# 4_-_IO_Socket_2.net
KiCad netlist of a schematic drawn in Altium Designer
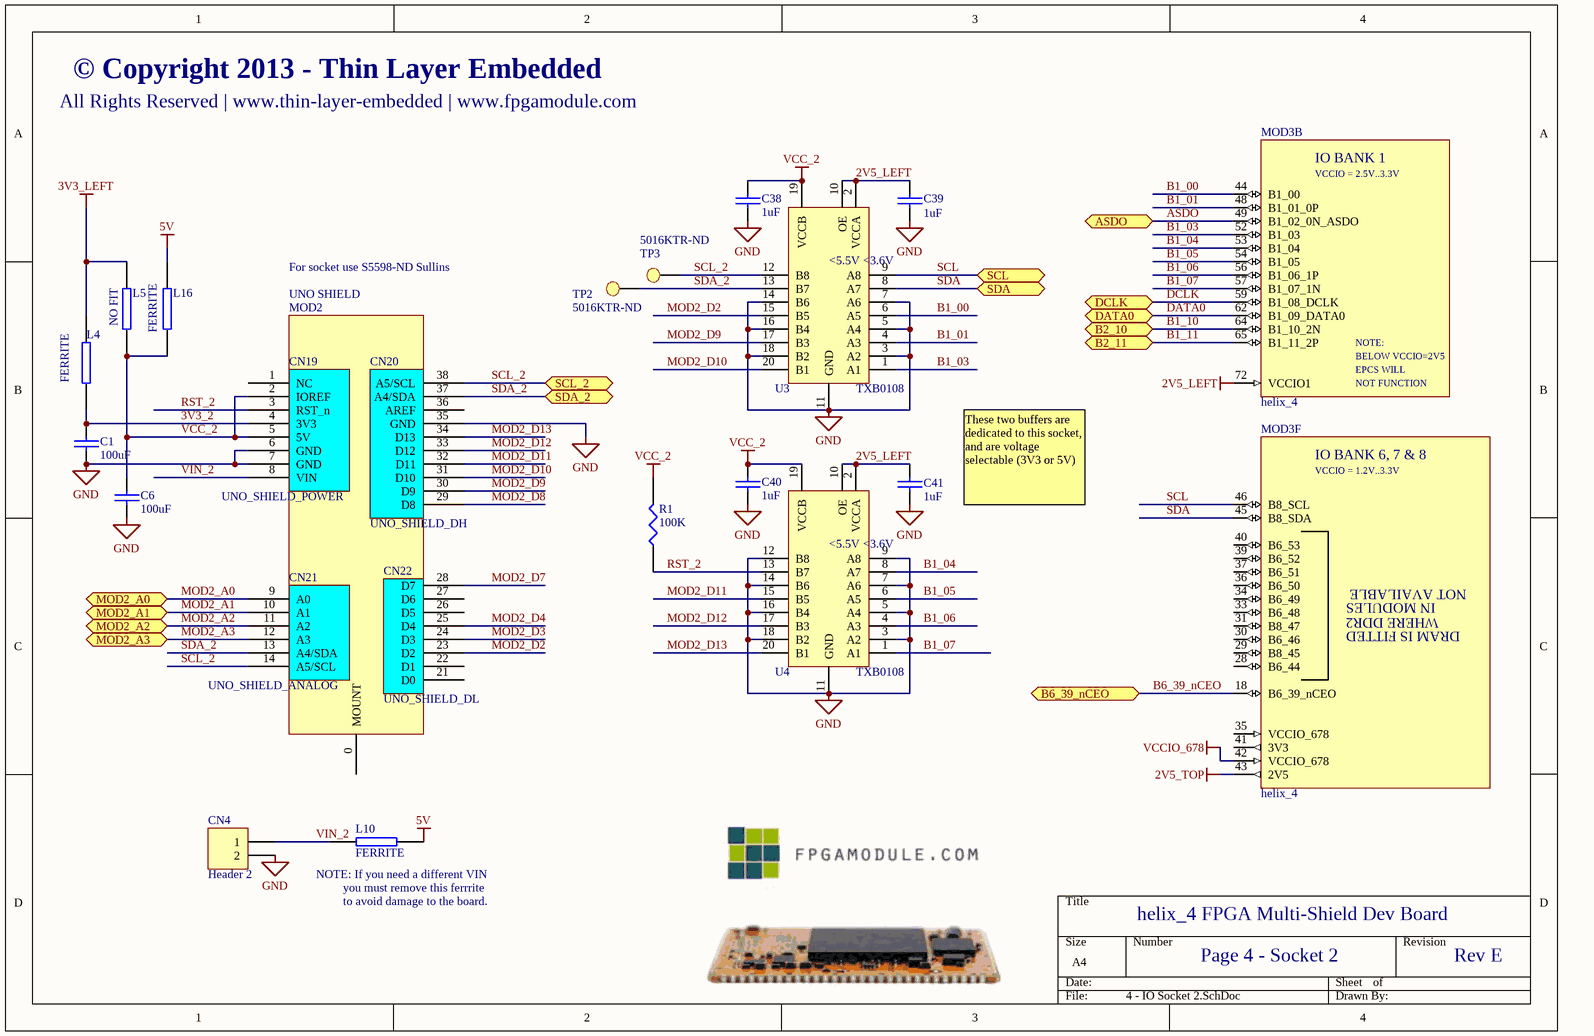
[diagram p0: 4 - IO Socket 2.SchDoc]

(export (version "E")
  (design (tool "Eeschema 10.0.6"))
  (components
    (comp (ref "C1")
      (value "100uF")
      (footprint "1210")
      (description "Capacitor")
      (libsource (lib "*") (part "CAP"))
    )
    (comp (ref "C6")
      (value "100uF")
      (footprint "1210")
      (description "Capacitor")
      (libsource (lib "*") (part "CAP"))
    )
    (comp (ref "C38")
      (value "1uF")
      (footprint "0805")
      (description "Capacitor")
      (libsource (lib "*") (part "CAP"))
    )
    (comp (ref "C39")
      (value "1uF")
      (footprint "0805")
      (description "Capacitor")
      (libsource (lib "*") (part "CAP"))
    )
    (comp (ref "C40")
      (value "1uF")
      (footprint "0805")
      (description "Capacitor")
      (libsource (lib "*") (part "CAP"))
    )
    (comp (ref "C41")
      (value "1uF")
      (footprint "0805")
      (description "Capacitor")
      (libsource (lib "*") (part "CAP"))
    )
    (comp (ref "CN4")
      (value "Header 2")
      (footprint "HDR1X2")
      (description "Header, 2-Pin")
      (fields (field (name "PUBLISHER") "Altium Limited"))
      (libsource (lib "Miscellaneous Connectors") (part "Header 2"))
    )
    (comp (ref "CN19")
      (value "UNO_SHIELD_POWER")
      (footprint "UNO_SHIELD_POWER")
      (libsource (lib "master_library") (part "UNO_SHIELD_POWER"))
    )
    (comp (ref "CN20")
      (value "UNO_SHIELD_DH")
      (footprint "UNO_SHIELD_DH")
      (libsource (lib "master_library") (part "UNO_SHIELD_DH"))
    )
    (comp (ref "CN21")
      (value "UNO_SHIELD_ANALOG")
      (footprint "UNO_SHIELD_ANALOG")
      (libsource (lib "master_library") (part "UNO_SHIELD_ANALOG"))
    )
    (comp (ref "CN22")
      (value "UNO_SHIELD_DL")
      (footprint "UNO_SHIELD_DL")
      (libsource (lib "master_library") (part "UNO_SHIELD_DL"))
    )
    (comp (ref "L4") (value "FERRITE") (footprint "0805") (libsource (lib "*") (part "FERRITE")))
    (comp (ref "L5")
      (value "NO FIT")
      (footprint "0805")
      (description "FERRITE")
      (libsource (lib "*") (part "FERRITE"))
    )
    (comp (ref "L10") (value "FERRITE") (footprint "0805") (libsource (lib "*") (part "FERRITE")))
    (comp (ref "L16") (value "FERRITE") (footprint "0805") (libsource (lib "*") (part "FERRITE")))
    (comp (ref "MOD2")
      (value "UNO SHIELD")
      (footprint "UNO_SHIELD_MECH")
      (libsource (lib "master_library") (part "UNO_SHIELD_MECH"))
    )
    (comp (ref "MOD3")
      (value "helix_4")
      (footprint "HELIX_4_LCC104_HOST")
      (libsource (lib "master_library") (part "helix_4 Rev C Module"))
    )
    (comp (ref "R1") (value "100K") (footprint "0805") (libsource (lib "*") (part "RES1")))
    (comp (ref "TP2")
      (value "Test Point")
      (footprint "TEST_POINT")
      (fields (field (name "SUPPLIER PART NUMBER 2") "5016KTR-ND"))
      (libsource (lib "motion tracker r2") (part "Test Point"))
    )
    (comp (ref "TP3")
      (value "Test Point")
      (footprint "TEST_POINT")
      (fields (field (name "SUPPLIER PART NUMBER 2") "5016KTR-ND"))
      (libsource (lib "motion tracker r2") (part "Test Point"))
    )
    (comp (ref "U3")
      (value "TXB0108")
      (footprint "TSSOP20")
      (description "TI Bir-dir buffer")
      (libsource (lib "master_library") (part "TXB0108"))
    )
    (comp (ref "U4")
      (value "TXB0108")
      (footprint "TSSOP20")
      (description "TI Bir-dir buffer")
      (libsource (lib "master_library") (part "TXB0108"))
    )
  )
  (nets
    (net (code "1") (name "/3V3_2") (class "Default")
      (node (ref "C1") (pin "1") (pinfunction "1_1") (pintype "passive"))
      (node (ref "CN19") (pin "4") (pinfunction "3V3_4") (pintype "passive"))
      (node (ref "L4") (pin "2") (pinfunction "2_2") (pintype "passive"))
    )
    (net (code "2") (name "/ASDO") (class "Default")
      (node (ref "MOD3") (pin "49") (pinfunction "B1_02_0N_ASDO_49") (pintype "bidirectional"))
    )
    (net (code "3") (name "/B1_00") (class "Default")
      (node (ref "MOD3") (pin "44") (pinfunction "B1_00_44") (pintype "bidirectional"))
      (node (ref "U3") (pin "6") (pinfunction "A5_6") (pintype "passive"))
    )
    (net (code "4") (name "/B1_01") (class "Default")
      (node (ref "MOD3") (pin "48") (pinfunction "B1_01_0P_48") (pintype "bidirectional"))
      (node (ref "U3") (pin "4") (pinfunction "A3_4") (pintype "passive"))
    )
    (net (code "5") (name "/B1_03") (class "Default")
      (node (ref "MOD3") (pin "52") (pinfunction "B1_03_52") (pintype "bidirectional"))
      (node (ref "U3") (pin "1") (pinfunction "A1_1") (pintype "passive"))
    )
    (net (code "6") (name "/B1_04") (class "Default")
      (node (ref "MOD3") (pin "53") (pinfunction "B1_04_53") (pintype "bidirectional"))
      (node (ref "U4") (pin "8") (pinfunction "A7_8") (pintype "passive"))
    )
    (net (code "7") (name "/B1_05") (class "Default")
      (node (ref "MOD3") (pin "54") (pinfunction "B1_05_54") (pintype "bidirectional"))
      (node (ref "U4") (pin "6") (pinfunction "A5_6") (pintype "passive"))
    )
    (net (code "8") (name "/B1_06") (class "Default")
      (node (ref "MOD3") (pin "56") (pinfunction "B1_06_1P_56") (pintype "bidirectional"))
      (node (ref "U4") (pin "4") (pinfunction "A3_4") (pintype "passive"))
    )
    (net (code "9") (name "/B1_07") (class "Default")
      (node (ref "MOD3") (pin "57") (pinfunction "B1_07_1N_57") (pintype "bidirectional"))
      (node (ref "U4") (pin "1") (pinfunction "A1_1") (pintype "passive"))
    )
    (net (code "10") (name "/B1_10") (class "Default")
      (node (ref "MOD3") (pin "64") (pinfunction "B1_10_2N_64") (pintype "bidirectional"))
    )
    (net (code "11") (name "/B1_11") (class "Default")
      (node (ref "MOD3") (pin "65") (pinfunction "B1_11_2P_65") (pintype "bidirectional"))
    )
    (net (code "12") (name "/B6_39_nCEO") (class "Default")
      (node (ref "MOD3") (pin "18") (pinfunction "B6_39_nCEO_18") (pintype "bidirectional"))
    )
    (net (code "13") (name "/DATA0") (class "Default")
      (node (ref "MOD3") (pin "62") (pinfunction "B1_09_DATA0_62") (pintype "bidirectional"))
    )
    (net (code "14") (name "/DCLK") (class "Default")
      (node (ref "MOD3") (pin "59") (pinfunction "B1_08_DCLK_59") (pintype "bidirectional"))
    )
    (net (code "15") (name "/MOD2_A0") (class "Default")
      (node (ref "CN21") (pin "9") (pinfunction "A0_9") (pintype "passive"))
    )
    (net (code "16") (name "/MOD2_A1") (class "Default")
      (node (ref "CN21") (pin "10") (pinfunction "A1_10") (pintype "passive"))
    )
    (net (code "17") (name "/MOD2_A2") (class "Default")
      (node (ref "CN21") (pin "11") (pinfunction "A2_11") (pintype "passive"))
    )
    (net (code "18") (name "/MOD2_A3") (class "Default")
      (node (ref "CN21") (pin "12") (pinfunction "A3_12") (pintype "passive"))
    )
    (net (code "19") (name "/MOD2_D2") (class "Default")
      (node (ref "CN22") (pin "23") (pinfunction "D2_23") (pintype "passive"))
      (node (ref "U3") (pin "15") (pinfunction "B5_15") (pintype "passive"))
    )
    (net (code "20") (name "/MOD2_D3") (class "Default")
      (node (ref "CN22") (pin "24") (pinfunction "D3_24") (pintype "passive"))
    )
    (net (code "21") (name "/MOD2_D4") (class "Default")
      (node (ref "CN22") (pin "25") (pinfunction "D4_25") (pintype "passive"))
    )
    (net (code "22") (name "/MOD2_D7") (class "Default")
      (node (ref "CN22") (pin "28") (pinfunction "D7_28") (pintype "passive"))
    )
    (net (code "23") (name "/MOD2_D8") (class "Default")
      (node (ref "CN20") (pin "29") (pinfunction "D8_29") (pintype "passive"))
    )
    (net (code "24") (name "/MOD2_D9") (class "Default")
      (node (ref "CN20") (pin "30") (pinfunction "D9_30") (pintype "passive"))
      (node (ref "U3") (pin "17") (pinfunction "B3_17") (pintype "passive"))
    )
    (net (code "25") (name "/MOD2_D10") (class "Default")
      (node (ref "CN20") (pin "31") (pinfunction "D10_31") (pintype "passive"))
      (node (ref "U3") (pin "20") (pinfunction "B1_20") (pintype "passive"))
    )
    (net (code "26") (name "/MOD2_D11") (class "Default")
      (node (ref "CN20") (pin "32") (pinfunction "D11_32") (pintype "passive"))
      (node (ref "U4") (pin "15") (pinfunction "B5_15") (pintype "passive"))
    )
    (net (code "27") (name "/MOD2_D12") (class "Default")
      (node (ref "CN20") (pin "33") (pinfunction "D12_33") (pintype "passive"))
      (node (ref "U4") (pin "17") (pinfunction "B3_17") (pintype "passive"))
    )
    (net (code "28") (name "/MOD2_D13") (class "Default")
      (node (ref "CN20") (pin "34") (pinfunction "D13_34") (pintype "passive"))
      (node (ref "U4") (pin "20") (pinfunction "B1_20") (pintype "passive"))
    )
    (net (code "29") (name "/RST_2") (class "Default")
      (node (ref "CN19") (pin "3") (pinfunction "RST_n_3") (pintype "passive"))
      (node (ref "R1") (pin "1") (pinfunction "1_1") (pintype "passive"))
      (node (ref "U4") (pin "13") (pinfunction "B7_13") (pintype "passive"))
    )
    (net (code "30") (name "/SCL") (class "Default")
      (node (ref "MOD3") (pin "46") (pinfunction "B8_SCL_46") (pintype "bidirectional"))
      (node (ref "U3") (pin "9") (pinfunction "A8_9") (pintype "passive"))
    )
    (net (code "31") (name "/SCL_2") (class "Default")
      (node (ref "CN20") (pin "38") (pinfunction "A5/SCL_38") (pintype "passive"))
      (node (ref "CN21") (pin "14") (pinfunction "A5/SCL_14") (pintype "passive"))
      (node (ref "TP3") (pin "1") (pinfunction "1_1") (pintype "passive"))
      (node (ref "U3") (pin "12") (pinfunction "B8_12") (pintype "passive"))
    )
    (net (code "32") (name "/SDA") (class "Default")
      (node (ref "MOD3") (pin "45") (pinfunction "B8_SDA_45") (pintype "bidirectional"))
      (node (ref "U3") (pin "8") (pinfunction "A7_8") (pintype "passive"))
    )
    (net (code "33") (name "/SDA_2") (class "Default")
      (node (ref "CN20") (pin "37") (pinfunction "A4/SDA_37") (pintype "passive"))
      (node (ref "CN21") (pin "13") (pinfunction "A4/SDA_13") (pintype "passive"))
      (node (ref "TP2") (pin "1") (pinfunction "1_1") (pintype "passive"))
      (node (ref "U3") (pin "13") (pinfunction "B7_13") (pintype "passive"))
    )
    (net (code "34") (name "/VIN_2") (class "Default")
      (node (ref "CN19") (pin "8") (pinfunction "VIN_8") (pintype "passive"))
      (node (ref "CN4") (pin "1") (pinfunction "1_1") (pintype "passive"))
      (node (ref "L10") (pin "2") (pinfunction "2_2") (pintype "passive"))
    )
    (net (code "35") (name "2V5_LEFT") (class "Default")
      (node (ref "C39") (pin "2") (pinfunction "2_2") (pintype "passive"))
      (node (ref "C41") (pin "2") (pinfunction "2_2") (pintype "passive"))
      (node (ref "MOD3") (pin "72") (pinfunction "VCCIO1_72") (pintype "input"))
      (node (ref "U3") (pin "10") (pinfunction "OE_10") (pintype "passive"))
      (node (ref "U3") (pin "2") (pinfunction "VCCA_2") (pintype "passive"))
      (node (ref "U4") (pin "10") (pinfunction "OE_10") (pintype "passive"))
      (node (ref "U4") (pin "2") (pinfunction "VCCA_2") (pintype "passive"))
    )
    (net (code "36") (name "2V5_TOP") (class "Default")
      (node (ref "MOD3") (pin "43") (pinfunction "2V5_43") (pintype "output"))
    )
    (net (code "37") (name "3V3_LEFT") (class "Default")
      (node (ref "L4") (pin "1") (pinfunction "1_1") (pintype "passive"))
      (node (ref "L5") (pin "1") (pinfunction "1_1") (pintype "passive"))
    )
    (net (code "38") (name "5V") (class "Default")
      (node (ref "L10") (pin "1") (pinfunction "1_1") (pintype "passive"))
      (node (ref "L16") (pin "1") (pinfunction "1_1") (pintype "passive"))
    )
    (net (code "39") (name "GND") (class "Default")
      (node (ref "C1") (pin "2") (pinfunction "2_2") (pintype "passive"))
      (node (ref "C38") (pin "1") (pinfunction "1_1") (pintype "passive"))
      (node (ref "C39") (pin "1") (pinfunction "1_1") (pintype "passive"))
      (node (ref "C40") (pin "1") (pinfunction "1_1") (pintype "passive"))
      (node (ref "C41") (pin "1") (pinfunction "1_1") (pintype "passive"))
      (node (ref "C6") (pin "2") (pinfunction "2_2") (pintype "passive"))
      (node (ref "CN19") (pin "6") (pinfunction "GND_6") (pintype "passive"))
      (node (ref "CN19") (pin "7") (pinfunction "GND_7") (pintype "passive"))
      (node (ref "CN20") (pin "35") (pinfunction "GND_35") (pintype "passive"))
      (node (ref "CN4") (pin "2") (pinfunction "2_2") (pintype "passive"))
      (node (ref "U3") (pin "11") (pinfunction "GND_11") (pintype "passive"))
      (node (ref "U3") (pin "14") (pinfunction "B6_14") (pintype "passive"))
      (node (ref "U3") (pin "16") (pinfunction "B4_16") (pintype "passive"))
      (node (ref "U3") (pin "18") (pinfunction "B2_18") (pintype "passive"))
      (node (ref "U3") (pin "3") (pinfunction "A2_3") (pintype "passive"))
      (node (ref "U3") (pin "5") (pinfunction "A4_5") (pintype "passive"))
      (node (ref "U3") (pin "7") (pinfunction "A6_7") (pintype "passive"))
      (node (ref "U4") (pin "11") (pinfunction "GND_11") (pintype "passive"))
      (node (ref "U4") (pin "12") (pinfunction "B8_12") (pintype "passive"))
      (node (ref "U4") (pin "14") (pinfunction "B6_14") (pintype "passive"))
      (node (ref "U4") (pin "16") (pinfunction "B4_16") (pintype "passive"))
      (node (ref "U4") (pin "18") (pinfunction "B2_18") (pintype "passive"))
      (node (ref "U4") (pin "3") (pinfunction "A2_3") (pintype "passive"))
      (node (ref "U4") (pin "5") (pinfunction "A4_5") (pintype "passive"))
      (node (ref "U4") (pin "7") (pinfunction "A6_7") (pintype "passive"))
      (node (ref "U4") (pin "9") (pinfunction "A8_9") (pintype "passive"))
    )
    (net (code "40") (name "VCCIO_678") (class "Default")
      (node (ref "MOD3") (pin "42") (pinfunction "VCCIO_678_42") (pintype "input"))
    )
    (net (code "41") (name "VCC_2") (class "Default")
      (node (ref "C38") (pin "2") (pinfunction "2_2") (pintype "passive"))
      (node (ref "C40") (pin "2") (pinfunction "2_2") (pintype "passive"))
      (node (ref "C6") (pin "1") (pinfunction "1_1") (pintype "passive"))
      (node (ref "CN19") (pin "2") (pinfunction "IOREF_2") (pintype "passive"))
      (node (ref "CN19") (pin "5") (pinfunction "5V_5") (pintype "passive"))
      (node (ref "L16") (pin "2") (pinfunction "2_2") (pintype "passive"))
      (node (ref "L5") (pin "2") (pinfunction "2_2") (pintype "passive"))
      (node (ref "R1") (pin "2") (pinfunction "2_2") (pintype "passive"))
      (node (ref "U3") (pin "19") (pinfunction "VCCB_19") (pintype "passive"))
      (node (ref "U4") (pin "19") (pinfunction "VCCB_19") (pintype "passive"))
    )
    (net (code "42") (name "unconnected-(CN19-NC-Pad1)") (class "Default")
      (node (ref "CN19") (pin "1") (pinfunction "NC_1") (pintype "passive"))
    )
    (net (code "43") (name "unconnected-(CN20-AREF-Pad36)") (class "Default")
      (node (ref "CN20") (pin "36") (pinfunction "AREF_36") (pintype "passive"))
    )
    (net (code "44") (name "unconnected-(CN22-D0-Pad21)") (class "Default")
      (node (ref "CN22") (pin "21") (pinfunction "D0_21") (pintype "passive"))
    )
    (net (code "45") (name "unconnected-(CN22-D1-Pad22)") (class "Default")
      (node (ref "CN22") (pin "22") (pinfunction "D1_22") (pintype "passive"))
    )
    (net (code "46") (name "unconnected-(CN22-D5-Pad26)") (class "Default")
      (node (ref "CN22") (pin "26") (pinfunction "D5_26") (pintype "passive"))
    )
    (net (code "47") (name "unconnected-(CN22-D6-Pad27)") (class "Default")
      (node (ref "CN22") (pin "27") (pinfunction "D6_27") (pintype "passive"))
    )
    (net (code "48") (name "unconnected-(MOD2-MOUNT-Pad0)") (class "Default")
      (node (ref "MOD2") (pin "0") (pinfunction "MOUNT_0") (pintype "passive"))
    )
    (net (code "49") (name "unconnected-(MOD3F-3V3-Pad41)") (class "Default")
      (node (ref "MOD3") (pin "41") (pinfunction "3V3_41") (pintype "output"))
    )
    (net (code "50") (name "unconnected-(MOD3F-B6_44-Pad28)") (class "Default")
      (node (ref "MOD3") (pin "28") (pinfunction "B6_44_28") (pintype "bidirectional"))
    )
    (net (code "51") (name "unconnected-(MOD3F-B6_46-Pad30)") (class "Default")
      (node (ref "MOD3") (pin "30") (pinfunction "B6_46_30") (pintype "bidirectional"))
    )
    (net (code "52") (name "unconnected-(MOD3F-B6_48-Pad33)") (class "Default")
      (node (ref "MOD3") (pin "33") (pinfunction "B6_48_33") (pintype "bidirectional"))
    )
    (net (code "53") (name "unconnected-(MOD3F-B6_49-Pad34)") (class "Default")
      (node (ref "MOD3") (pin "34") (pinfunction "B6_49_34") (pintype "bidirectional"))
    )
    (net (code "54") (name "unconnected-(MOD3F-B6_50-Pad36)") (class "Default")
      (node (ref "MOD3") (pin "36") (pinfunction "B6_50_36") (pintype "bidirectional"))
    )
    (net (code "55") (name "unconnected-(MOD3F-B6_51-Pad37)") (class "Default")
      (node (ref "MOD3") (pin "37") (pinfunction "B6_51_37") (pintype "bidirectional"))
    )
    (net (code "56") (name "unconnected-(MOD3F-B6_52-Pad39)") (class "Default")
      (node (ref "MOD3") (pin "39") (pinfunction "B6_52_39") (pintype "bidirectional"))
    )
    (net (code "57") (name "unconnected-(MOD3F-B6_53-Pad40)") (class "Default")
      (node (ref "MOD3") (pin "40") (pinfunction "B6_53_40") (pintype "bidirectional"))
    )
    (net (code "58") (name "unconnected-(MOD3F-B8_45-Pad29)") (class "Default")
      (node (ref "MOD3") (pin "29") (pinfunction "B8_45_29") (pintype "bidirectional"))
    )
    (net (code "59") (name "unconnected-(MOD3F-B8_47-Pad31)") (class "Default")
      (node (ref "MOD3") (pin "31") (pinfunction "B8_47_31") (pintype "bidirectional"))
    )
    (net (code "60") (name "unconnected-(MOD3F-VCCIO_678-Pad35)") (class "Default")
      (node (ref "MOD3") (pin "35") (pinfunction "VCCIO_678_35") (pintype "input"))
    )
  )
)
